# Sheet2.net
KiCad netlist of a schematic drawn in Altium Designer
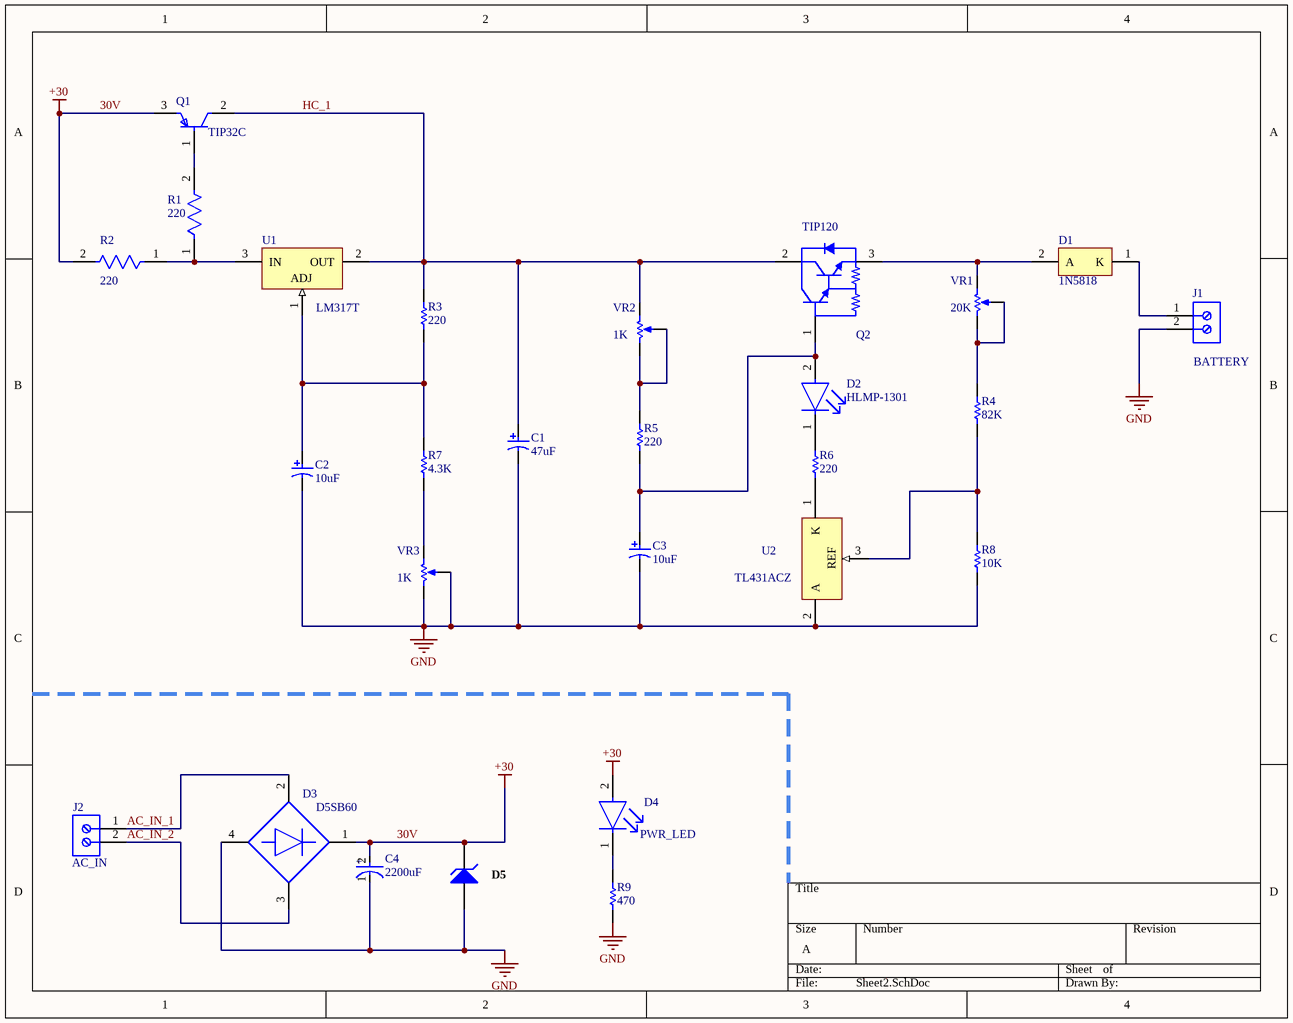
[diagram p0: Sheet2.SchDoc]

(export (version "E")
  (design (tool "Eeschema 10.0.6"))
  (components
    (comp (ref "C1")
      (value "47uF")
      (footprint "CAPPR55-200-1100X500X1200")
      (description "Aluminum Electrolytic Capacitor, 10 uF, +/- 20%, 50 V, -40 to 85 degC, 2-Pin THD, RoHS, Bulk")
      (fields (field (name "MANUFACTURER") "Panasonic") (field (name "TOLERANCE") "20%"))
      (libsource (lib "Altium Content Vault") (part "CAP-P-2"))
    )
    (comp (ref "C2")
      (value "10uF")
      (footprint "CAPPR55-200-1100X500X1200")
      (description "Aluminum Electrolytic Capacitor, 10 uF, +/- 20%, 50 V, -40 to 85 degC, 2-Pin THD, RoHS, Bulk")
      (fields (field (name "MANUFACTURER") "Panasonic") (field (name "TOLERANCE") "20%"))
      (libsource (lib "Altium Content Vault") (part "CAP-P-2"))
    )
    (comp (ref "C3")
      (value "10uF")
      (footprint "CAPPR55-200-1100X500X1200")
      (description "Aluminum Electrolytic Capacitor, 10 uF, +/- 20%, 50 V, -40 to 85 degC, 2-Pin THD, RoHS, Bulk")
      (fields (field (name "MANUFACTURER") "Panasonic") (field (name "TOLERANCE") "20%"))
      (libsource (lib "Altium Content Vault") (part "CAP-P-2"))
    )
    (comp (ref "C4")
      (value "2200uF")
      (footprint "FP-RAD-TH-D_12_5_0_5-L_40-MFG")
      (description "Aluminum Electrolytic Capacitors (Radial Lead Type) AEC-Q200 Qualified 2200uF ±20% 35V")
      (fields (field (name "TOLERANCE") "20%") (field (name "VOLTAGE") "35V"))
      (libsource (lib "Altium Content Vault") (part "203bc49f2ac43e59fd269a8c329ed05"))
    )
    (comp (ref "D1")
      (value "1N5818")
      (footprint "ONSC-AXIAL_LEAD-2-59-10_P")
      (description "Rectifier, 2-Pin Axial_Lead, Pb-Free, Bulk Bag")
      (fields (field (name "MANUFACTURER") "On Semiconductor"))
      (libsource (lib "Altium Content Vault") (part "ONSC-D-K1A2-2_A"))
    )
    (comp (ref "D2")
      (value "HLMP-1301")
      (footprint "FP-HLMP-1301-MFG")
      (description "LED RED DIFFUSED T-1 T/H")
      (fields
        (field (name "OCTOPART") "https://octopart.com/hlmp-1301-broadcom-71130345")
        (field (name "MANUFACTURER") "Broadcom")
      )
      (libsource (lib "Altium Content Vault") (part "8706943c75ba83719d021d2fdc84c58"))
    )
    (comp (ref "D3")
      (value "D5SB60")
      (footprint "FP-GBU-MFG")
      (description "BRIDGE RECT 1PHASE 800V 3.9A GBU")
      (fields (field (name "MANUFACTURER") "Vishay") (field (name "MANUFACTURER PART NUMBER") "GBU8K-E3/45"))
      (libsource (lib "Altium Content Vault") (part "e379534fd63a4ee30460fa8b2d5b875"))
    )
    (comp (ref "D4")
      (value "PWR_LED")
      (footprint "FP-HLMP-1503-MFG")
      (description "LED GREEN DIFFUSED T-1 T/H")
      (fields (field (name "MANUFACTURER") "Broadcom") (field (name "MANUFACTURER PART NUMBER") "HLMP-1503"))
      (libsource (lib "Altium Content Vault") (part "8706943c75ba83719d021d2fdc84c58"))
    )
    (comp (ref "D5")
      (value "1N4732A")
      (footprint "FAIR-DO-41-2_V")
      (description "Zener Diode, 4.7V, 1W, 5%, -65 to 200 degC, 2-Pin DO-41, Body 2.72 x 5.2 mm, RoHS")
      (fields (field (name "TOLERANCE") "5%") (field (name "MANUFACTURER") "Fairchild Semiconductor"))
      (libsource (lib "Altium Content Vault") (part "FAIR-DZEN-A1K2-2"))
    )
    (comp (ref "J1")
      (value "BATTERY")
      (footprint "PHOE-1714955_V")
      (description "PC Terminal Block, Pitch 6.35 mm, 1 x 2 Position, Height 21.5 mm, Tail Lenght 5.1 mm, RoHS, Bulk")
      (fields (field (name "MANUFACTURER") "Phoenix Contact"))
      (libsource (lib "Altium Content Vault") (part "CN-1P-F-TB2"))
    )
    (comp (ref "J2")
      (value "AC_IN")
      (footprint "PHOE-1714955_V")
      (description "PC Terminal Block, Pitch 6.35 mm, 1 x 2 Position, Height 21.5 mm, Tail Lenght 5.1 mm, RoHS, Bulk")
      (fields (field (name "MANUFACTURER") "Phoenix Contact"))
      (libsource (lib "Altium Content Vault") (part "CN-1P-F-TB2"))
    )
    (comp (ref "Q1")
      (value "TIP32C")
      (footprint "FP-TO-220-P0A0015988-MFG")
      (description "TRANS PNP 100V 3A TO-220")
      (fields
        (field (name "MANUFACTURER") "STMicroelectronics")
        (field (name "OCTOPART") "https://octopart.com/tip32c-stmicroelectronics-353617")
      )
      (libsource (lib "Altium Content Vault") (part "802a31d42ca070764d097f06bc9597f"))
    )
    (comp (ref "Q2")
      (value "TIP120")
      (footprint "ONSC-TO-220-3-221A-09")
      (description "Plastic Medium-Power, Complementary Silicon Transistor, 3-Pin TO-220, Tube")
      (fields (field (name "MANUFACTURER") "On Semiconductor"))
      (libsource (lib "Altium Content Vault") (part "ONSC-DT-NPN-B1C2E3-3_A"))
    )
    (comp (ref "R1")
      (value "220")
      (footprint "FP-SP3A-MFG")
      (description "RES 10 OHM 5% 4W AXIAL")
      (fields (field (name "TOLERANCE") "5%"))
      (libsource (lib "Altium Content Vault") (part "1029c3af85768c4190bb7ad29bc67b5"))
    )
    (comp (ref "R2")
      (value "220")
      (footprint "FP-SP3A-MFG")
      (description "RES 10 OHM 5% 4W AXIAL")
      (fields (field (name "TOLERANCE") "5%"))
      (libsource (lib "Altium Content Vault") (part "1029c3af85768c4190bb7ad29bc67b5"))
    )
    (comp (ref "R3")
      (value "220")
      (footprint "RESA60-630X240")
      (description "Axial Resistor, 1 KOhm, +/- 1%, 250 mW, -55 to 155 degC, 2-Pin THD, RoHS, Bulk")
      (fields (field (name "TOLERANCE") "1%"))
      (libsource (lib "Altium Content Vault") (part "RES-2"))
    )
    (comp (ref "R4")
      (value "82K")
      (footprint "RESA60-630X240")
      (description "Axial Resistor, 1 KOhm, +/- 1%, 250 mW, -55 to 155 degC, 2-Pin THD, RoHS, Bulk")
      (fields (field (name "TOLERANCE") "1%"))
      (libsource (lib "Altium Content Vault") (part "RES-2"))
    )
    (comp (ref "R5")
      (value "220")
      (footprint "RESA60-630X240")
      (description "Axial Resistor, 1 KOhm, +/- 1%, 250 mW, -55 to 155 degC, 2-Pin THD, RoHS, Bulk")
      (fields (field (name "TOLERANCE") "1%"))
      (libsource (lib "Altium Content Vault") (part "RES-2"))
    )
    (comp (ref "R6")
      (value "220")
      (footprint "RESA60-630X240")
      (description "Axial Resistor, 1 KOhm, +/- 1%, 250 mW, -55 to 155 degC, 2-Pin THD, RoHS, Bulk")
      (fields (field (name "TOLERANCE") "1%"))
      (libsource (lib "Altium Content Vault") (part "RES-2"))
    )
    (comp (ref "R7")
      (value "4.3K")
      (footprint "RESA60-630X240")
      (description "Axial Resistor, 1 KOhm, +/- 1%, 250 mW, -55 to 155 degC, 2-Pin THD, RoHS, Bulk")
      (fields (field (name "TOLERANCE") "1%"))
      (libsource (lib "Altium Content Vault") (part "RES-2"))
    )
    (comp (ref "R8")
      (value "10K")
      (footprint "RESA60-630X240")
      (description "Axial Resistor, 1 KOhm, +/- 1%, 250 mW, -55 to 155 degC, 2-Pin THD, RoHS, Bulk")
      (fields (field (name "TOLERANCE") "1%"))
      (libsource (lib "Altium Content Vault") (part "RES-2"))
    )
    (comp (ref "R9")
      (value "470")
      (footprint "RESA60-630X240")
      (description "Axial Resistor, 1 KOhm, +/- 1%, 250 mW, -55 to 155 degC, 2-Pin THD, RoHS, Bulk")
      (fields (field (name "TOLERANCE") "1%"))
      (libsource (lib "Altium Content Vault") (part "RES-2"))
    )
    (comp (ref "U1")
      (value "LM317T")
      (footprint "TO-220")
      (description "1.5A, 1.2V to 37V Adjustable Voltage Regulator, 3-Pin TO-220")
      (libsource (lib "Altium Content Vault") (part "PM-REG-117-SIL3"))
    )
    (comp (ref "U2")
      (value "TL431ACZ")
      (footprint "TO-92")
      (description "Programmable Voltage Reference, 2.5 to 36V, 3-Pin TO-92")
      (libsource (lib "Altium Content Vault") (part "PM-REF-431-SIL3"))
    )
    (comp (ref "VR1")
      (value "20K")
      (footprint "BOUR-3852A-282-103AL-3_V")
      (description "Diameter Panel Control, 10 KOhm, +/- 10%, 2 W, -1 to 125 degC, 3-Pin THD, RoHS, Bulk")
      (fields (field (name "TOLERANCE") "±10%") (field (name "MANUFACTURER") "Bourns"))
      (libsource (lib "Altium Content Vault") (part "RES-POT-3"))
    )
    (comp (ref "VR2")
      (value "1K")
      (footprint "BOUR-3852A-282-103AL-3_V")
      (description "Diameter Panel Control, 10 KOhm, +/- 10%, 2 W, -1 to 125 degC, 3-Pin THD, RoHS, Bulk")
      (fields (field (name "TOLERANCE") "±10%") (field (name "MANUFACTURER") "Bourns"))
      (libsource (lib "Altium Content Vault") (part "RES-POT-3"))
    )
    (comp (ref "VR3")
      (value "1K")
      (footprint "BOUR-3852A-282-103AL-3_V")
      (description "Diameter Panel Control, 10 KOhm, +/- 10%, 2 W, -1 to 125 degC, 3-Pin THD, RoHS, Bulk")
      (fields (field (name "TOLERANCE") "±10%") (field (name "MANUFACTURER") "Bourns"))
      (libsource (lib "Altium Content Vault") (part "RES-POT-3"))
    )
  )
  (nets
    (net (code "1") (name "+30") (class "Default")
      (node (ref "C4") (pin "2") (pinfunction "A_2") (pintype "passive"))
      (node (ref "D3") (pin "1") (pinfunction "+_1") (pintype "passive"))
      (node (ref "D4") (pin "2") (pinfunction "A_2") (pintype "passive"))
      (node (ref "D5") (pin "2") (pinfunction "K_2") (pintype "passive"))
      (node (ref "Q1") (pin "3") (pinfunction "E_3") (pintype "passive"))
      (node (ref "R2") (pin "2") (pinfunction "2_2") (pintype "passive"))
    )
    (net (code "2") (name "/AC_IN_1") (class "Default")
      (node (ref "D3") (pin "2") (pinfunction "1_~_2") (pintype "passive"))
      (node (ref "J2") (pin "1") (pinfunction "1_1") (pintype "passive"))
    )
    (net (code "3") (name "/AC_IN_2") (class "Default")
      (node (ref "D3") (pin "3") (pinfunction "2_~_3") (pintype "passive"))
      (node (ref "J2") (pin "2") (pinfunction "2_2") (pintype "passive"))
    )
    (net (code "4") (name "/HC_1") (class "Default")
      (node (ref "C1") (pin "1") (pinfunction "1_1") (pintype "passive"))
      (node (ref "Q1") (pin "2") (pinfunction "C_2") (pintype "passive"))
      (node (ref "Q2") (pin "2") (pinfunction "C_2") (pintype "passive"))
      (node (ref "R3") (pin "2") (pinfunction "2_2") (pintype "passive"))
      (node (ref "U1") (pin "2") (pinfunction "OUT_2") (pintype "power_in"))
      (node (ref "VR2") (pin "1") (pinfunction "CCW_1") (pintype "passive"))
    )
    (net (code "5") (name "GND") (class "Default")
      (node (ref "C1") (pin "2") (pinfunction "2_2") (pintype "passive"))
      (node (ref "C2") (pin "2") (pinfunction "2_2") (pintype "passive"))
      (node (ref "C3") (pin "2") (pinfunction "2_2") (pintype "passive"))
      (node (ref "C4") (pin "1") (pinfunction "C_1") (pintype "passive"))
      (node (ref "D3") (pin "4") (pinfunction "-_4") (pintype "passive"))
      (node (ref "D5") (pin "1") (pinfunction "A_1") (pintype "passive"))
      (node (ref "J1") (pin "2") (pinfunction "2_2") (pintype "passive"))
      (node (ref "R8") (pin "1") (pinfunction "1_1") (pintype "passive"))
      (node (ref "R9") (pin "1") (pinfunction "1_1") (pintype "passive"))
      (node (ref "U2") (pin "2") (pinfunction "A_2") (pintype "passive"))
      (node (ref "VR3") (pin "2") (pinfunction "S_2") (pintype "passive"))
      (node (ref "VR3") (pin "3") (pinfunction "CW_3") (pintype "passive"))
    )
    (net (code "6") (name "Net-(D1-A)") (class "Default")
      (node (ref "D1") (pin "2") (pinfunction "A_2") (pintype "passive"))
      (node (ref "Q2") (pin "3") (pinfunction "E_3") (pintype "passive"))
      (node (ref "VR1") (pin "1") (pinfunction "CCW_1") (pintype "passive"))
    )
    (net (code "7") (name "Net-(D1-K)") (class "Default")
      (node (ref "D1") (pin "1") (pinfunction "K_1") (pintype "passive"))
      (node (ref "J1") (pin "1") (pinfunction "1_1") (pintype "passive"))
    )
    (net (code "8") (name "Net-(D2-A)") (class "Default")
      (node (ref "C3") (pin "1") (pinfunction "1_1") (pintype "passive"))
      (node (ref "D2") (pin "2") (pinfunction "A_2") (pintype "passive"))
      (node (ref "Q2") (pin "1") (pinfunction "B_1") (pintype "passive"))
      (node (ref "R5") (pin "1") (pinfunction "1_1") (pintype "passive"))
    )
    (net (code "9") (name "Net-(D2-C)") (class "Default")
      (node (ref "D2") (pin "1") (pinfunction "C_1") (pintype "passive"))
      (node (ref "R6") (pin "2") (pinfunction "2_2") (pintype "passive"))
    )
    (net (code "10") (name "Net-(D4-C)") (class "Default")
      (node (ref "D4") (pin "1") (pinfunction "C_1") (pintype "passive"))
      (node (ref "R9") (pin "2") (pinfunction "2_2") (pintype "passive"))
    )
    (net (code "11") (name "Net-(Q1-B)") (class "Default")
      (node (ref "Q1") (pin "1") (pinfunction "B_1") (pintype "passive"))
      (node (ref "R1") (pin "2") (pinfunction "2_2") (pintype "passive"))
    )
    (net (code "12") (name "Net-(U1-ADJ)") (class "Default")
      (node (ref "C2") (pin "1") (pinfunction "1_1") (pintype "passive"))
      (node (ref "R3") (pin "1") (pinfunction "1_1") (pintype "passive"))
      (node (ref "R7") (pin "2") (pinfunction "2_2") (pintype "passive"))
      (node (ref "U1") (pin "1") (pinfunction "ADJ_1") (pintype "input"))
    )
    (net (code "13") (name "Net-(U1-IN)") (class "Default")
      (node (ref "R1") (pin "1") (pinfunction "1_1") (pintype "passive"))
      (node (ref "R2") (pin "1") (pinfunction "1_1") (pintype "passive"))
      (node (ref "U1") (pin "3") (pinfunction "IN_3") (pintype "power_in"))
    )
    (net (code "14") (name "Net-(U2-K)") (class "Default")
      (node (ref "R6") (pin "1") (pinfunction "1_1") (pintype "passive"))
      (node (ref "U2") (pin "1") (pinfunction "K_1") (pintype "passive"))
    )
    (net (code "15") (name "Net-(U2-REF)") (class "Default")
      (node (ref "R4") (pin "1") (pinfunction "1_1") (pintype "passive"))
      (node (ref "R8") (pin "2") (pinfunction "2_2") (pintype "passive"))
      (node (ref "U2") (pin "3") (pinfunction "REF_3") (pintype "input"))
    )
    (net (code "16") (name "Net-(VR1-CW)") (class "Default")
      (node (ref "R4") (pin "2") (pinfunction "2_2") (pintype "passive"))
      (node (ref "VR1") (pin "2") (pinfunction "S_2") (pintype "passive"))
      (node (ref "VR1") (pin "3") (pinfunction "CW_3") (pintype "passive"))
    )
    (net (code "17") (name "Net-(VR2-CW)") (class "Default")
      (node (ref "R5") (pin "2") (pinfunction "2_2") (pintype "passive"))
      (node (ref "VR2") (pin "2") (pinfunction "S_2") (pintype "passive"))
      (node (ref "VR2") (pin "3") (pinfunction "CW_3") (pintype "passive"))
    )
    (net (code "18") (name "Net-(VR3-CCW)") (class "Default")
      (node (ref "R7") (pin "1") (pinfunction "1_1") (pintype "passive"))
      (node (ref "VR3") (pin "1") (pinfunction "CCW_1") (pintype "passive"))
    )
  )
)
